# Sheet1.net
KiCad netlist of a schematic drawn in Altium Designer
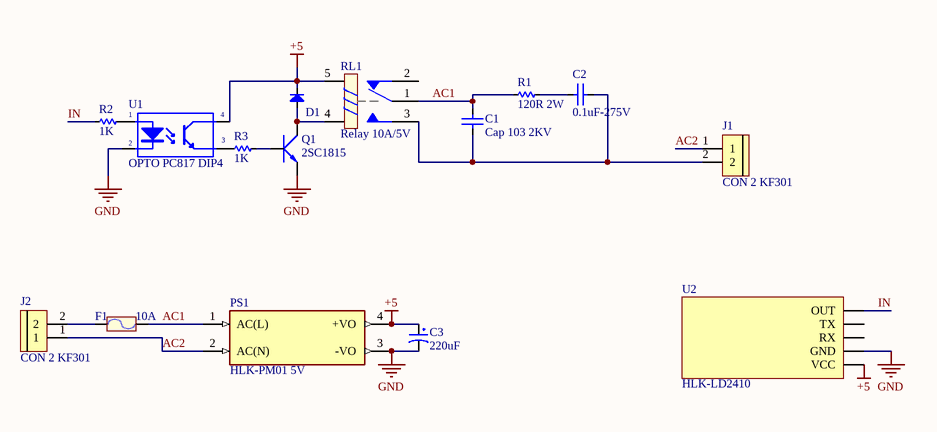
[diagram p0: Sheet1.SchDoc]

(export (version "E")
  (design (tool "Eeschema 10.0.6"))
  (components
    (comp (ref "C1")
      (value "Cap 103 2KV")
      (footprint "Cap 7.5mm")
      (description "Capacitor Ceramic 2KV")
      (libsource (lib "iuh-thuc-hanh") (part "Cap 103 2KV"))
    )
    (comp (ref "C2")
      (value "0.1uF-275V")
      (footprint "Cap 15mm")
      (description "Capacitor")
      (libsource (lib "iuh-thuc-hanh") (part "CN"))
    )
    (comp (ref "C3")
      (value "220uF")
      (footprint "Tu hoa 5mm")
      (description "Cắm")
      (libsource (lib "Altium_Lib_by_KhueNguyenCreator") (part "Tu Hoa 220uF 16V 6x11"))
    )
    (comp (ref "D1")
      (value "Diode")
      (footprint "DIO-1A")
      (description "Default Diode")
      (fields (field (name "PUBLISHER") "Altium Limited"))
      (libsource (lib "LIBRARY1") (part "Diode"))
    )
    (comp (ref "F1")
      (value "10A")
      (footprint "Fuse vertical")
      (description "Fuse")
      (fields (field (name "DESIGNED BY") "VanDungEvn"))
      (libsource (lib "iuh-thuc-hanh") (part "Fuse"))
    )
    (comp (ref "J1")
      (value "CON 2 KF301")
      (footprint "Con 2 KF301 5.08")
      (description "Cắm")
      (libsource (lib "Altium_Lib_by_KhueNguyenCreator") (part "CON 2 KF301"))
    )
    (comp (ref "J2")
      (value "CON 2 KF301")
      (footprint "Con 2 KF301 5.08")
      (description "Cắm")
      (libsource (lib "") (part "CON 2 KF301_1"))
    )
    (comp (ref "PS1")
      (value "HLK-PM01 5V")
      (footprint "CONV_HLK-PM01")
      (description "220VAC to 5V 3W")
      (fields (field (name "MF") "Hi-link") (field (name "MP") "HLK-20M12"))
      (libsource (lib "iuh-thuc-hanh") (part "CONV HLK-PM01"))
    )
    (comp (ref "Q1")
      (value "2SC1815")
      (footprint "TO92-123")
      (description "NPN 600mW, ECB")
      (libsource (lib "LIBRARY1") (part "2SC1815"))
    )
    (comp (ref "R1") (value "120R 2W") (footprint "R2WD") (libsource (lib "iuh-thuc-hanh") (part "Res")))
    (comp (ref "R2") (value "1K") (footprint "RES-1/4W") (libsource (lib "iuh-thuc-hanh") (part "Res")))
    (comp (ref "R3") (value "1K") (footprint "RES-1/4W") (libsource (lib "iuh-thuc-hanh") (part "Res")))
    (comp (ref "RL1")
      (value "Relay 10A/5V")
      (footprint "RELAY 5")
      (description "Relay SPDT,10A - 12VDC 5 Pin")
      (libsource (lib "LIBRARY1") (part "Relay 5"))
    )
    (comp (ref "U1")
      (value "OPTO PC817 DIP4")
      (footprint "DIP4")
      (description "Single Opto")
      (libsource (lib "Altium_Lib_by_KhueNguyenCreator") (part "OPTO PC817 DIP4"))
    )
    (comp (ref "U2")
      (value "HLK-LD2410")
      (footprint "HLK-LD2410")
      (description "HLK-LD2410B-P Cam bien hien dien")
      (libsource (lib "iuh-thuc-hanh") (part "HLK-LD2410"))
    )
  )
  (nets
    (net (code "1") (name "+5") (class "Default")
      (node (ref "C3") (pin "1") (pinfunction "1_1") (pintype "passive"))
      (node (ref "D1") (pin "2") (pinfunction "K_2") (pintype "passive"))
      (node (ref "PS1") (pin "4") (pinfunction "+VO_4") (pintype "output"))
      (node (ref "RL1") (pin "5") (pinfunction "5_5") (pintype "passive"))
      (node (ref "U1") (pin "4") (pinfunction "C_4") (pintype "passive"))
      (node (ref "U2") (pin "5") (pinfunction "VCC_5") (pintype "passive"))
    )
    (net (code "2") (name "/AC1") (class "Default")
      (node (ref "C1") (pin "1") (pinfunction "1_1") (pintype "passive"))
      (node (ref "F1") (pin "2") (pinfunction "2_2") (pintype "passive"))
      (node (ref "PS1") (pin "1") (pinfunction "AC(L)_1") (pintype "input"))
      (node (ref "R1") (pin "2") (pinfunction "2_2") (pintype "passive"))
      (node (ref "RL1") (pin "1") (pinfunction "1_1") (pintype "passive"))
    )
    (net (code "3") (name "/AC2") (class "Default")
      (node (ref "J1") (pin "1") (pinfunction "1_1") (pintype "passive"))
      (node (ref "J2") (pin "1") (pinfunction "1_1") (pintype "passive"))
      (node (ref "PS1") (pin "2") (pinfunction "AC(N)_2") (pintype "input"))
    )
    (net (code "4") (name "/IN") (class "Default")
      (node (ref "R2") (pin "2") (pinfunction "2_2") (pintype "passive"))
      (node (ref "U2") (pin "1") (pinfunction "OUT_1") (pintype "passive"))
    )
    (net (code "5") (name "GND") (class "Default")
      (node (ref "C3") (pin "2") (pinfunction "2_2") (pintype "passive"))
      (node (ref "PS1") (pin "3") (pinfunction "-VO_3") (pintype "output"))
      (node (ref "Q1") (pin "1") (pinfunction "E_1") (pintype "passive"))
      (node (ref "U1") (pin "2") (pinfunction "K_2") (pintype "passive"))
      (node (ref "U2") (pin "4") (pinfunction "GND_4") (pintype "passive"))
    )
    (net (code "6") (name "Net-(C1-Pad2)") (class "Default")
      (node (ref "C1") (pin "2") (pinfunction "2_2") (pintype "passive"))
      (node (ref "C2") (pin "1") (pinfunction "1_1") (pintype "passive"))
      (node (ref "J1") (pin "2") (pinfunction "2_2") (pintype "passive"))
      (node (ref "RL1") (pin "3") (pinfunction "3_3") (pintype "passive"))
    )
    (net (code "7") (name "Net-(C2-Pad2)") (class "Default")
      (node (ref "C2") (pin "2") (pinfunction "2_2") (pintype "passive"))
      (node (ref "R1") (pin "1") (pinfunction "1_1") (pintype "passive"))
    )
    (net (code "8") (name "Net-(D1-A)") (class "Default")
      (node (ref "D1") (pin "1") (pinfunction "A_1") (pintype "passive"))
      (node (ref "Q1") (pin "2") (pinfunction "C_2") (pintype "passive"))
      (node (ref "RL1") (pin "4") (pinfunction "4_4") (pintype "passive"))
    )
    (net (code "9") (name "Net-(F1-Pad1)") (class "Default")
      (node (ref "F1") (pin "1") (pinfunction "1_1") (pintype "passive"))
      (node (ref "J2") (pin "2") (pinfunction "2_2") (pintype "passive"))
    )
    (net (code "10") (name "Net-(Q1-B)") (class "Default")
      (node (ref "Q1") (pin "3") (pinfunction "B_3") (pintype "passive"))
      (node (ref "R3") (pin "1") (pinfunction "1_1") (pintype "passive"))
    )
    (net (code "11") (name "Net-(U1-A)") (class "Default")
      (node (ref "R2") (pin "1") (pinfunction "1_1") (pintype "passive"))
      (node (ref "U1") (pin "1") (pinfunction "A_1") (pintype "passive"))
    )
    (net (code "12") (name "Net-(U1-E)") (class "Default")
      (node (ref "R3") (pin "2") (pinfunction "2_2") (pintype "passive"))
      (node (ref "U1") (pin "3") (pinfunction "E_3") (pintype "passive"))
    )
    (net (code "13") (name "unconnected-(RL1-Pad2)") (class "Default")
      (node (ref "RL1") (pin "2") (pinfunction "2_2") (pintype "passive"))
    )
    (net (code "14") (name "unconnected-(U2-RX-Pad3)") (class "Default")
      (node (ref "U2") (pin "3") (pinfunction "RX_3") (pintype "passive"))
    )
    (net (code "15") (name "unconnected-(U2-TX-Pad2)") (class "Default")
      (node (ref "U2") (pin "2") (pinfunction "TX_2") (pintype "passive"))
    )
  )
)
